# Segbot_schematic_v1.net
KiCad netlist of a schematic drawn in EAGLE
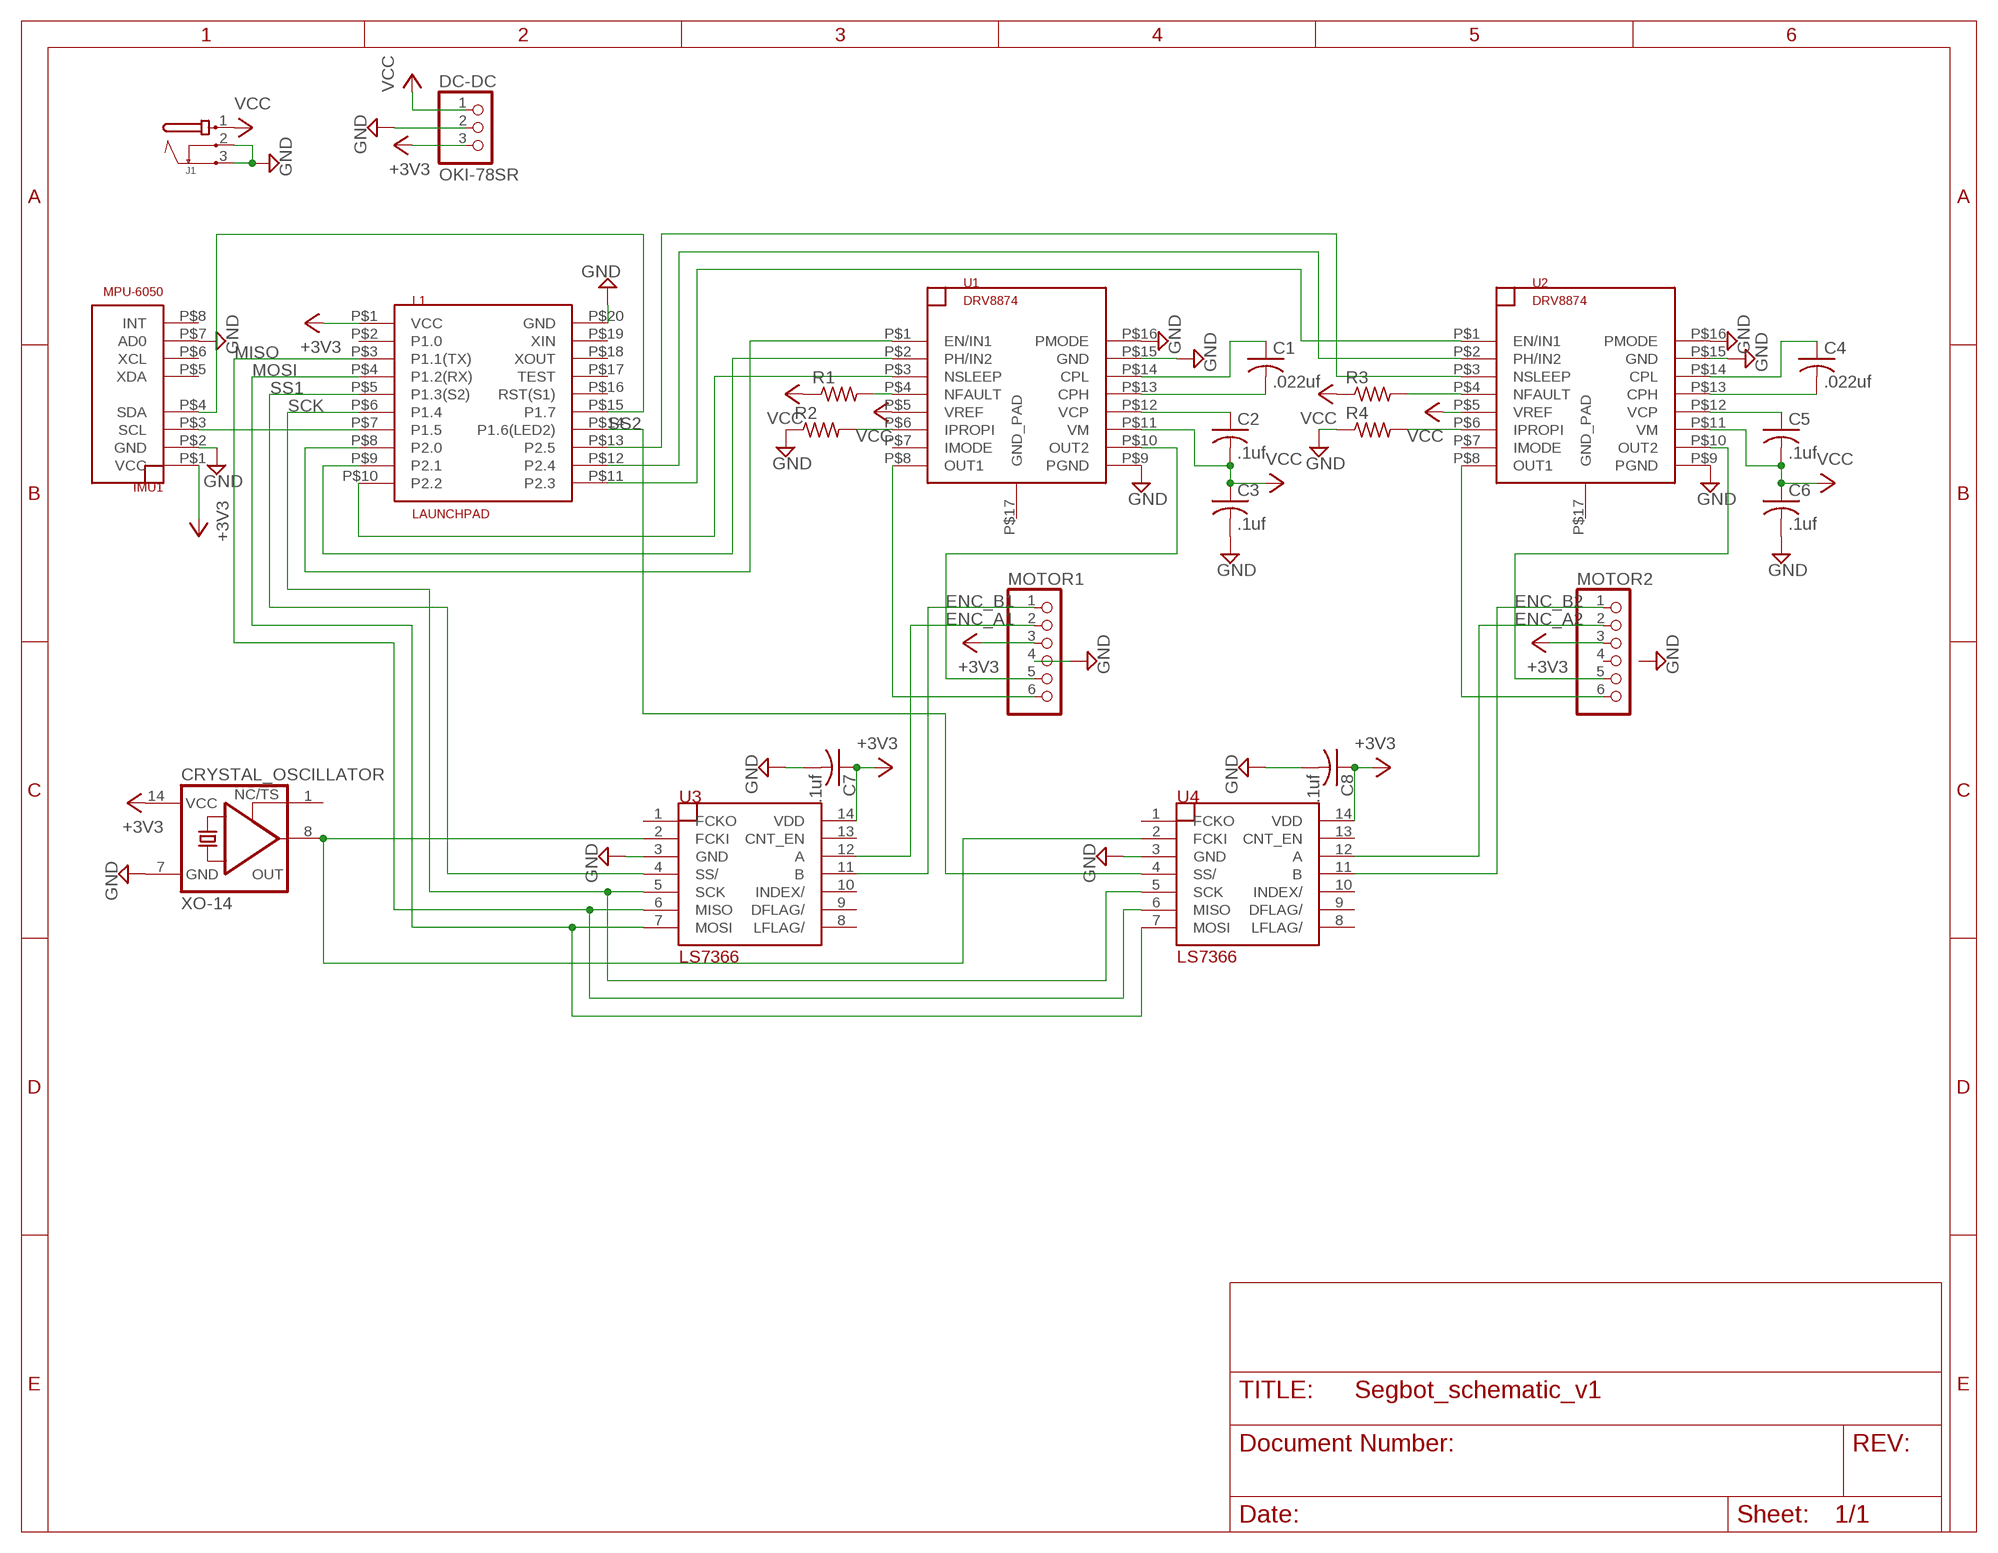
[diagram p0: schematic, sheet 1]

(export (version "E")
  (design (tool "Eeschema 10.0.6"))
  (components
    (comp (ref "C1")
      (value ".022uf")
      (footprint "eagle-import:C025-024X044")
      (libsource (lib "eagle-import") (part "resistor_C-US025-024X044"))
    )
    (comp (ref "C2")
      (value ".1uf")
      (footprint "eagle-import:C025-024X044")
      (libsource (lib "eagle-import") (part "resistor_C-US025-024X044"))
    )
    (comp (ref "C3")
      (value ".1uf")
      (footprint "eagle-import:C025-024X044")
      (libsource (lib "eagle-import") (part "resistor_C-US025-024X044"))
    )
    (comp (ref "C4")
      (value ".022uf")
      (footprint "eagle-import:C025-024X044")
      (libsource (lib "eagle-import") (part "resistor_C-US025-024X044"))
    )
    (comp (ref "C5")
      (value ".1uf")
      (footprint "eagle-import:C025-024X044")
      (libsource (lib "eagle-import") (part "resistor_C-US025-024X044"))
    )
    (comp (ref "C6")
      (value ".1uf")
      (footprint "eagle-import:C025-024X044")
      (libsource (lib "eagle-import") (part "resistor_C-US025-024X044"))
    )
    (comp (ref "C7")
      (value ".1uf")
      (footprint "eagle-import:C1206")
      (libsource (lib "eagle-import") (part "C-USC1206"))
    )
    (comp (ref "C8")
      (value ".1uf")
      (footprint "eagle-import:C1206")
      (libsource (lib "eagle-import") (part "C-USC1206"))
    )
    (comp (ref "CRYSTAL_OSCILLATOR")
      (value "XO-14")
      (footprint "eagle-import:DIL14S")
      (libsource (lib "eagle-import") (part "XO-14"))
    )
    (comp (ref "DC-DC")
      (value "OKI-78SR")
      (footprint "eagle-import:1X03")
      (libsource (lib "eagle-import") (part "PINHD-1X3"))
    )
    (comp (ref "IMU1")
      (value "MPU-6050")
      (footprint "eagle-import:MPU6050_MODULE")
      (libsource (lib "eagle-import") (part "MPU6050_MODULE"))
    )
    (comp (ref "J1")
      (value "JACK-PMS")
      (footprint "eagle-import:JACK-PMS")
      (libsource (lib "eagle-import") (part "JACK-PMS"))
    )
    (comp (ref "L1")
      (value "LAUNCHPAD")
      (footprint "eagle-import:LAUNCHPAD")
      (libsource (lib "eagle-import") (part "LAUNCHPAD"))
    )
    (comp (ref "MOTOR1")
      (value "PINHD-1X6")
      (footprint "eagle-import:1X06")
      (libsource (lib "eagle-import") (part "PINHD-1X6"))
    )
    (comp (ref "MOTOR2")
      (value "PINHD-1X6")
      (footprint "eagle-import:1X06")
      (libsource (lib "eagle-import") (part "PINHD-1X6"))
    )
    (comp (ref "R1")
      (value "R-US_R1206")
      (footprint "eagle-import:R1206")
      (libsource (lib "eagle-import") (part "R-US_R1206"))
    )
    (comp (ref "R2")
      (value "R-US_R1206")
      (footprint "eagle-import:R1206")
      (libsource (lib "eagle-import") (part "R-US_R1206"))
    )
    (comp (ref "R3")
      (value "R-US_R1206")
      (footprint "eagle-import:R1206")
      (libsource (lib "eagle-import") (part "R-US_R1206"))
    )
    (comp (ref "R4")
      (value "R-US_R1206")
      (footprint "eagle-import:R1206")
      (libsource (lib "eagle-import") (part "R-US_R1206"))
    )
    (comp (ref "U1")
      (value "DRV8874")
      (footprint "eagle-import:HTSSOP16")
      (libsource (lib "eagle-import") (part "DRV8874"))
    )
    (comp (ref "U2")
      (value "DRV8874")
      (footprint "eagle-import:HTSSOP16")
      (libsource (lib "eagle-import") (part "DRV8874"))
    )
    (comp (ref "U3")
      (value "LS7366")
      (footprint "eagle-import:SO14")
      (libsource (lib "eagle-import") (part "LS7366R"))
    )
    (comp (ref "U4")
      (value "LS7366")
      (footprint "eagle-import:SO14")
      (libsource (lib "eagle-import") (part "LS7366R"))
    )
  )
  (nets
    (net (code "1") (name "+3V3") (class "Default")
      (node (ref "C7") (pin "1") (pinfunction "1_1") (pintype "passive"))
      (node (ref "C8") (pin "1") (pinfunction "1_1") (pintype "passive"))
      (node (ref "CRYSTAL_OSCILLATOR") (pin "14") (pinfunction "VCC_14") (pintype "power_in"))
      (node (ref "DC-DC") (pin "3") (pinfunction "3_3") (pintype "passive"))
      (node (ref "IMU1") (pin "P$1") (pinfunction "VCC_P$1") (pintype "bidirectional"))
      (node (ref "L1") (pin "P$1") (pinfunction "VCC_P$1") (pintype "bidirectional"))
      (node (ref "MOTOR1") (pin "3") (pinfunction "3_3") (pintype "passive"))
      (node (ref "MOTOR2") (pin "3") (pinfunction "3_3") (pintype "passive"))
      (node (ref "U3") (pin "14") (pinfunction "VDD_14") (pintype "bidirectional"))
      (node (ref "U4") (pin "14") (pinfunction "VDD_14") (pintype "bidirectional"))
    )
    (net (code "2") (name "/ENC_A1") (class "Default")
      (node (ref "MOTOR1") (pin "2") (pinfunction "2_2") (pintype "passive"))
      (node (ref "U3") (pin "12") (pinfunction "A_12") (pintype "bidirectional"))
    )
    (net (code "3") (name "/ENC_A2") (class "Default")
      (node (ref "MOTOR2") (pin "2") (pinfunction "2_2") (pintype "passive"))
      (node (ref "U4") (pin "12") (pinfunction "A_12") (pintype "bidirectional"))
    )
    (net (code "4") (name "/ENC_B1") (class "Default")
      (node (ref "MOTOR1") (pin "1") (pinfunction "1_1") (pintype "passive"))
      (node (ref "U3") (pin "11") (pinfunction "B_11") (pintype "bidirectional"))
    )
    (net (code "5") (name "/ENC_B2") (class "Default")
      (node (ref "MOTOR2") (pin "1") (pinfunction "1_1") (pintype "passive"))
      (node (ref "U4") (pin "11") (pinfunction "B_11") (pintype "bidirectional"))
    )
    (net (code "6") (name "/MISO") (class "Default")
      (node (ref "L1") (pin "P$3") (pinfunction "P1.1(TX)_P$3") (pintype "bidirectional"))
      (node (ref "U3") (pin "6") (pinfunction "MISO_6") (pintype "bidirectional"))
      (node (ref "U4") (pin "6") (pinfunction "MISO_6") (pintype "bidirectional"))
    )
    (net (code "7") (name "/MOSI") (class "Default")
      (node (ref "L1") (pin "P$4") (pinfunction "P1.2(RX)_P$4") (pintype "bidirectional"))
      (node (ref "U3") (pin "7") (pinfunction "MOSI_7") (pintype "bidirectional"))
      (node (ref "U4") (pin "7") (pinfunction "MOSI_7") (pintype "bidirectional"))
    )
    (net (code "8") (name "/SCK") (class "Default")
      (node (ref "L1") (pin "P$6") (pinfunction "P1.4_P$6") (pintype "bidirectional"))
      (node (ref "U3") (pin "5") (pinfunction "SCK_5") (pintype "bidirectional"))
      (node (ref "U4") (pin "5") (pinfunction "SCK_5") (pintype "bidirectional"))
    )
    (net (code "9") (name "/SS1") (class "Default")
      (node (ref "L1") (pin "P$5") (pinfunction "P1.3(S2)_P$5") (pintype "bidirectional"))
      (node (ref "U3") (pin "4") (pinfunction "SS/_4") (pintype "bidirectional"))
    )
    (net (code "10") (name "/SS2") (class "Default")
      (node (ref "L1") (pin "P$14") (pinfunction "P1.6(LED2)_P$14") (pintype "bidirectional"))
      (node (ref "U4") (pin "4") (pinfunction "SS/_4") (pintype "bidirectional"))
    )
    (net (code "11") (name "GND") (class "Default")
      (node (ref "C3") (pin "2") (pinfunction "2_2") (pintype "passive"))
      (node (ref "C6") (pin "2") (pinfunction "2_2") (pintype "passive"))
      (node (ref "C7") (pin "2") (pinfunction "2_2") (pintype "passive"))
      (node (ref "C8") (pin "2") (pinfunction "2_2") (pintype "passive"))
      (node (ref "CRYSTAL_OSCILLATOR") (pin "7") (pinfunction "GND_7") (pintype "power_in"))
      (node (ref "DC-DC") (pin "2") (pinfunction "2_2") (pintype "passive"))
      (node (ref "IMU1") (pin "P$2") (pinfunction "GND_P$2") (pintype "bidirectional"))
      (node (ref "IMU1") (pin "P$7") (pinfunction "AD0_P$7") (pintype "bidirectional"))
      (node (ref "J1") (pin "2") (pinfunction "2_2") (pintype "passive"))
      (node (ref "J1") (pin "3") (pinfunction "3_3") (pintype "passive"))
      (node (ref "L1") (pin "P$20") (pinfunction "GND_P$20") (pintype "bidirectional"))
      (node (ref "MOTOR1") (pin "4") (pinfunction "4_4") (pintype "passive"))
      (node (ref "R2") (pin "1") (pinfunction "1_1") (pintype "passive"))
      (node (ref "R4") (pin "1") (pinfunction "1_1") (pintype "passive"))
      (node (ref "U1") (pin "P$15") (pinfunction "GND_P$15") (pintype "bidirectional"))
      (node (ref "U1") (pin "P$16") (pinfunction "PMODE_P$16") (pintype "bidirectional"))
      (node (ref "U1") (pin "P$9") (pinfunction "PGND_P$9") (pintype "bidirectional"))
      (node (ref "U2") (pin "P$15") (pinfunction "GND_P$15") (pintype "bidirectional"))
      (node (ref "U2") (pin "P$16") (pinfunction "PMODE_P$16") (pintype "bidirectional"))
      (node (ref "U2") (pin "P$9") (pinfunction "PGND_P$9") (pintype "bidirectional"))
      (node (ref "U3") (pin "3") (pinfunction "GND_3") (pintype "bidirectional"))
      (node (ref "U4") (pin "3") (pinfunction "GND_3") (pintype "bidirectional"))
    )
    (net (code "12") (name "Net-(CRYSTAL_OSCILLATOR-OUT)") (class "Default")
      (node (ref "CRYSTAL_OSCILLATOR") (pin "8") (pinfunction "OUT_8") (pintype "output"))
      (node (ref "U3") (pin "2") (pinfunction "FCKI_2") (pintype "bidirectional"))
      (node (ref "U4") (pin "2") (pinfunction "FCKI_2") (pintype "bidirectional"))
    )
    (net (code "13") (name "Net-(IMU1-SCL)") (class "Default")
      (node (ref "IMU1") (pin "P$3") (pinfunction "SCL_P$3") (pintype "bidirectional"))
      (node (ref "L1") (pin "P$7") (pinfunction "P1.5_P$7") (pintype "bidirectional"))
    )
    (net (code "14") (name "Net-(IMU1-SDA)") (class "Default")
      (node (ref "IMU1") (pin "P$4") (pinfunction "SDA_P$4") (pintype "bidirectional"))
      (node (ref "L1") (pin "P$15") (pinfunction "P1.7_P$15") (pintype "bidirectional"))
    )
    (net (code "15") (name "Net-(L1-P2.0)") (class "Default")
      (node (ref "L1") (pin "P$8") (pinfunction "P2.0_P$8") (pintype "bidirectional"))
      (node (ref "U1") (pin "P$1") (pinfunction "EN/IN1_P$1") (pintype "bidirectional"))
    )
    (net (code "16") (name "Net-(L1-P2.1)") (class "Default")
      (node (ref "L1") (pin "P$9") (pinfunction "P2.1_P$9") (pintype "bidirectional"))
      (node (ref "U1") (pin "P$2") (pinfunction "PH/IN2_P$2") (pintype "bidirectional"))
    )
    (net (code "17") (name "Net-(L1-P2.2)") (class "Default")
      (node (ref "L1") (pin "P$10") (pinfunction "P2.2_P$10") (pintype "bidirectional"))
      (node (ref "U1") (pin "P$3") (pinfunction "NSLEEP_P$3") (pintype "bidirectional"))
    )
    (net (code "18") (name "Net-(L1-P2.3)") (class "Default")
      (node (ref "L1") (pin "P$11") (pinfunction "P2.3_P$11") (pintype "bidirectional"))
      (node (ref "U2") (pin "P$1") (pinfunction "EN/IN1_P$1") (pintype "bidirectional"))
    )
    (net (code "19") (name "Net-(L1-P2.4)") (class "Default")
      (node (ref "L1") (pin "P$12") (pinfunction "P2.4_P$12") (pintype "bidirectional"))
      (node (ref "U2") (pin "P$2") (pinfunction "PH/IN2_P$2") (pintype "bidirectional"))
    )
    (net (code "20") (name "Net-(L1-P2.5)") (class "Default")
      (node (ref "L1") (pin "P$13") (pinfunction "P2.5_P$13") (pintype "bidirectional"))
      (node (ref "U2") (pin "P$3") (pinfunction "NSLEEP_P$3") (pintype "bidirectional"))
    )
    (net (code "21") (name "Net-(U1-CPH)") (class "Default")
      (node (ref "C1") (pin "2") (pinfunction "2_2") (pintype "passive"))
      (node (ref "U1") (pin "P$13") (pinfunction "CPH_P$13") (pintype "bidirectional"))
    )
    (net (code "22") (name "Net-(U1-CPL)") (class "Default")
      (node (ref "C1") (pin "1") (pinfunction "1_1") (pintype "passive"))
      (node (ref "U1") (pin "P$14") (pinfunction "CPL_P$14") (pintype "bidirectional"))
    )
    (net (code "23") (name "Net-(U1-IPROPI)") (class "Default")
      (node (ref "R2") (pin "2") (pinfunction "2_2") (pintype "passive"))
      (node (ref "U1") (pin "P$6") (pinfunction "IPROPI_P$6") (pintype "bidirectional"))
    )
    (net (code "24") (name "Net-(U1-NFAULT)") (class "Default")
      (node (ref "R1") (pin "2") (pinfunction "2_2") (pintype "passive"))
      (node (ref "U1") (pin "P$4") (pinfunction "NFAULT_P$4") (pintype "bidirectional"))
    )
    (net (code "25") (name "Net-(U1-OUT1)") (class "Default")
      (node (ref "MOTOR1") (pin "6") (pinfunction "6_6") (pintype "passive"))
      (node (ref "U1") (pin "P$8") (pinfunction "OUT1_P$8") (pintype "bidirectional"))
    )
    (net (code "26") (name "Net-(U1-OUT2)") (class "Default")
      (node (ref "MOTOR1") (pin "5") (pinfunction "5_5") (pintype "passive"))
      (node (ref "U1") (pin "P$10") (pinfunction "OUT2_P$10") (pintype "bidirectional"))
    )
    (net (code "27") (name "Net-(U1-VCP)") (class "Default")
      (node (ref "C2") (pin "1") (pinfunction "1_1") (pintype "passive"))
      (node (ref "U1") (pin "P$12") (pinfunction "VCP_P$12") (pintype "bidirectional"))
    )
    (net (code "28") (name "Net-(U2-CPH)") (class "Default")
      (node (ref "C4") (pin "2") (pinfunction "2_2") (pintype "passive"))
      (node (ref "U2") (pin "P$13") (pinfunction "CPH_P$13") (pintype "bidirectional"))
    )
    (net (code "29") (name "Net-(U2-CPL)") (class "Default")
      (node (ref "C4") (pin "1") (pinfunction "1_1") (pintype "passive"))
      (node (ref "U2") (pin "P$14") (pinfunction "CPL_P$14") (pintype "bidirectional"))
    )
    (net (code "30") (name "Net-(U2-IPROPI)") (class "Default")
      (node (ref "R4") (pin "2") (pinfunction "2_2") (pintype "passive"))
      (node (ref "U2") (pin "P$6") (pinfunction "IPROPI_P$6") (pintype "bidirectional"))
    )
    (net (code "31") (name "Net-(U2-NFAULT)") (class "Default")
      (node (ref "R3") (pin "2") (pinfunction "2_2") (pintype "passive"))
      (node (ref "U2") (pin "P$4") (pinfunction "NFAULT_P$4") (pintype "bidirectional"))
    )
    (net (code "32") (name "Net-(U2-OUT1)") (class "Default")
      (node (ref "MOTOR2") (pin "6") (pinfunction "6_6") (pintype "passive"))
      (node (ref "U2") (pin "P$8") (pinfunction "OUT1_P$8") (pintype "bidirectional"))
    )
    (net (code "33") (name "Net-(U2-OUT2)") (class "Default")
      (node (ref "MOTOR2") (pin "5") (pinfunction "5_5") (pintype "passive"))
      (node (ref "U2") (pin "P$10") (pinfunction "OUT2_P$10") (pintype "bidirectional"))
    )
    (net (code "34") (name "Net-(U2-VCP)") (class "Default")
      (node (ref "C5") (pin "1") (pinfunction "1_1") (pintype "passive"))
      (node (ref "U2") (pin "P$12") (pinfunction "VCP_P$12") (pintype "bidirectional"))
    )
    (net (code "35") (name "VCC") (class "Default")
      (node (ref "C2") (pin "2") (pinfunction "2_2") (pintype "passive"))
      (node (ref "C3") (pin "1") (pinfunction "1_1") (pintype "passive"))
      (node (ref "C5") (pin "2") (pinfunction "2_2") (pintype "passive"))
      (node (ref "C6") (pin "1") (pinfunction "1_1") (pintype "passive"))
      (node (ref "DC-DC") (pin "1") (pinfunction "1_1") (pintype "passive"))
      (node (ref "J1") (pin "1") (pinfunction "1_1") (pintype "passive"))
      (node (ref "R1") (pin "1") (pinfunction "1_1") (pintype "passive"))
      (node (ref "R3") (pin "1") (pinfunction "1_1") (pintype "passive"))
      (node (ref "U1") (pin "P$11") (pinfunction "VM_P$11") (pintype "bidirectional"))
      (node (ref "U1") (pin "P$5") (pinfunction "VREF_P$5") (pintype "bidirectional"))
      (node (ref "U2") (pin "P$11") (pinfunction "VM_P$11") (pintype "bidirectional"))
      (node (ref "U2") (pin "P$5") (pinfunction "VREF_P$5") (pintype "bidirectional"))
    )
    (net (code "36") (name "unconnected-(CRYSTAL_OSCILLATOR-TS-Pad1)") (class "Default")
      (node (ref "CRYSTAL_OSCILLATOR") (pin "1") (pinfunction "TS_1") (pintype "passive"))
    )
    (net (code "37") (name "unconnected-(IMU1-INT-PadP$8)") (class "Default")
      (node (ref "IMU1") (pin "P$8") (pinfunction "INT_P$8") (pintype "bidirectional"))
    )
    (net (code "38") (name "unconnected-(IMU1-XCL-PadP$6)") (class "Default")
      (node (ref "IMU1") (pin "P$6") (pinfunction "XCL_P$6") (pintype "bidirectional"))
    )
    (net (code "39") (name "unconnected-(IMU1-XDA-PadP$5)") (class "Default")
      (node (ref "IMU1") (pin "P$5") (pinfunction "XDA_P$5") (pintype "bidirectional"))
    )
    (net (code "40") (name "unconnected-(L1-P1.0-PadP$2)") (class "Default")
      (node (ref "L1") (pin "P$2") (pinfunction "P1.0_P$2") (pintype "bidirectional"))
    )
    (net (code "41") (name "unconnected-(L1-RST(S1)-PadP$16)") (class "Default")
      (node (ref "L1") (pin "P$16") (pinfunction "RST(S1)_P$16") (pintype "bidirectional"))
    )
    (net (code "42") (name "unconnected-(L1-TEST-PadP$17)") (class "Default")
      (node (ref "L1") (pin "P$17") (pinfunction "TEST_P$17") (pintype "bidirectional"))
    )
    (net (code "43") (name "unconnected-(L1-XIN-PadP$19)") (class "Default")
      (node (ref "L1") (pin "P$19") (pinfunction "XIN_P$19") (pintype "bidirectional"))
    )
    (net (code "44") (name "unconnected-(L1-XOUT-PadP$18)") (class "Default")
      (node (ref "L1") (pin "P$18") (pinfunction "XOUT_P$18") (pintype "bidirectional"))
    )
    (net (code "45") (name "unconnected-(MOTOR2-Pad4)") (class "Default")
      (node (ref "MOTOR2") (pin "4") (pinfunction "4_4") (pintype "passive"))
    )
    (net (code "46") (name "unconnected-(U1-GND_PAD-PadP$17)") (class "Default")
      (node (ref "U1") (pin "P$17") (pinfunction "GND_PAD_P$17") (pintype "bidirectional"))
    )
    (net (code "47") (name "unconnected-(U1-IMODE-PadP$7)") (class "Default")
      (node (ref "U1") (pin "P$7") (pinfunction "IMODE_P$7") (pintype "bidirectional"))
    )
    (net (code "48") (name "unconnected-(U2-GND_PAD-PadP$17)") (class "Default")
      (node (ref "U2") (pin "P$17") (pinfunction "GND_PAD_P$17") (pintype "bidirectional"))
    )
    (net (code "49") (name "unconnected-(U2-IMODE-PadP$7)") (class "Default")
      (node (ref "U2") (pin "P$7") (pinfunction "IMODE_P$7") (pintype "bidirectional"))
    )
    (net (code "50") (name "unconnected-(U3-CNT_EN-Pad13)") (class "Default")
      (node (ref "U3") (pin "13") (pinfunction "CNT_EN_13") (pintype "bidirectional"))
    )
    (net (code "51") (name "unconnected-(U3-DFLAG{slash}-Pad9)") (class "Default")
      (node (ref "U3") (pin "9") (pinfunction "DFLAG/_9") (pintype "bidirectional"))
    )
    (net (code "52") (name "unconnected-(U3-FCKO-Pad1)") (class "Default")
      (node (ref "U3") (pin "1") (pinfunction "FCKO_1") (pintype "bidirectional"))
    )
    (net (code "53") (name "unconnected-(U3-INDEX{slash}-Pad10)") (class "Default")
      (node (ref "U3") (pin "10") (pinfunction "INDEX/_10") (pintype "bidirectional"))
    )
    (net (code "54") (name "unconnected-(U3-LFLAG{slash}-Pad8)") (class "Default")
      (node (ref "U3") (pin "8") (pinfunction "LFLAG/_8") (pintype "bidirectional"))
    )
    (net (code "55") (name "unconnected-(U4-CNT_EN-Pad13)") (class "Default")
      (node (ref "U4") (pin "13") (pinfunction "CNT_EN_13") (pintype "bidirectional"))
    )
    (net (code "56") (name "unconnected-(U4-DFLAG{slash}-Pad9)") (class "Default")
      (node (ref "U4") (pin "9") (pinfunction "DFLAG/_9") (pintype "bidirectional"))
    )
    (net (code "57") (name "unconnected-(U4-FCKO-Pad1)") (class "Default")
      (node (ref "U4") (pin "1") (pinfunction "FCKO_1") (pintype "bidirectional"))
    )
    (net (code "58") (name "unconnected-(U4-INDEX{slash}-Pad10)") (class "Default")
      (node (ref "U4") (pin "10") (pinfunction "INDEX/_10") (pintype "bidirectional"))
    )
    (net (code "59") (name "unconnected-(U4-LFLAG{slash}-Pad8)") (class "Default")
      (node (ref "U4") (pin "8") (pinfunction "LFLAG/_8") (pintype "bidirectional"))
    )
  )
)
